# board.net
KiCad netlist of a schematic drawn in EAGLE
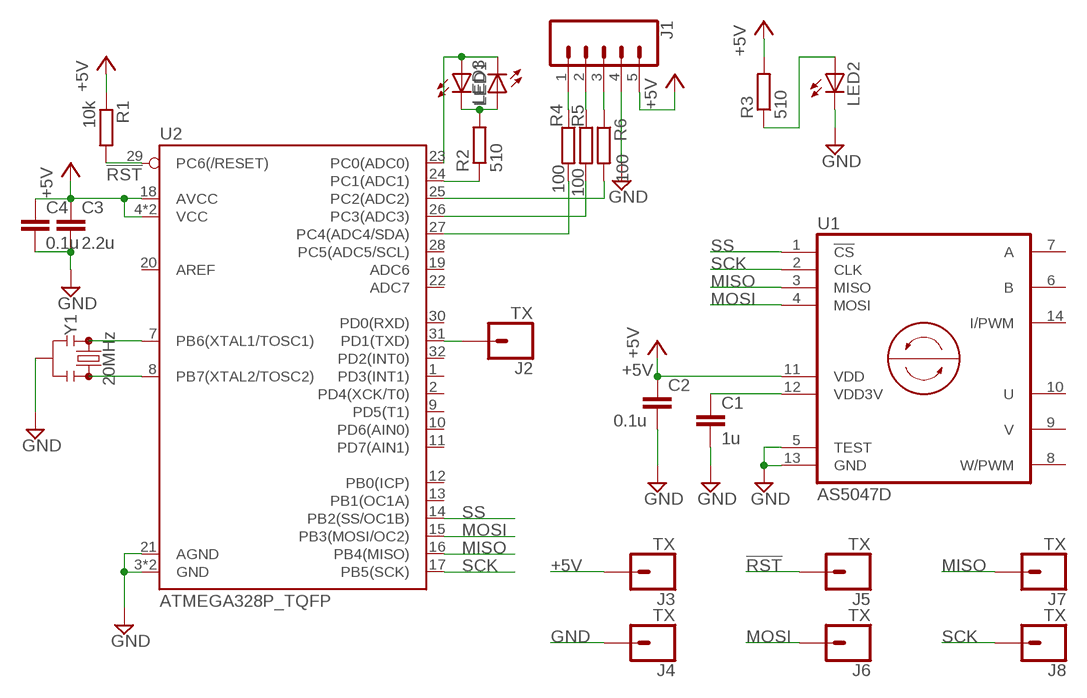
[diagram p0: schematic, sheet 1]

(export (version "E")
  (design (tool "Eeschema 10.0.6"))
  (components
    (comp (ref "C1")
      (value "1u")
      (footprint "eagle-import:C0603")
      (libsource (lib "eagle-import") (part "C-EUC0603"))
    )
    (comp (ref "C2")
      (value "0.1u")
      (footprint "eagle-import:C0603")
      (libsource (lib "eagle-import") (part "C-EUC0603"))
    )
    (comp (ref "C3")
      (value "2.2u")
      (footprint "eagle-import:C0603")
      (libsource (lib "eagle-import") (part "C-EUC0603"))
    )
    (comp (ref "C4")
      (value "0.1u")
      (footprint "eagle-import:C0603")
      (libsource (lib "eagle-import") (part "C-EUC0603"))
    )
    (comp (ref "J1")
      (value "CONN_05PTH_LONGPADS")
      (footprint "eagle-import:1X05_LONGPADS")
      (libsource (lib "eagle-import") (part "CONN_05PTH_LONGPADS"))
    )
    (comp (ref "J2")
      (value "TX")
      (footprint "eagle-import:1X01_NO_SILK")
      (libsource (lib "eagle-import") (part "CONN_01PTH_NO_SILK_YES_STOP"))
    )
    (comp (ref "J3")
      (value "TX")
      (footprint "eagle-import:1X01_NO_SILK")
      (libsource (lib "eagle-import") (part "CONN_01PTH_NO_SILK_YES_STOP"))
    )
    (comp (ref "J4")
      (value "TX")
      (footprint "eagle-import:1X01_NO_SILK")
      (libsource (lib "eagle-import") (part "CONN_01PTH_NO_SILK_YES_STOP"))
    )
    (comp (ref "J5")
      (value "TX")
      (footprint "eagle-import:1X01_NO_SILK")
      (libsource (lib "eagle-import") (part "CONN_01PTH_NO_SILK_YES_STOP"))
    )
    (comp (ref "J6")
      (value "TX")
      (footprint "eagle-import:1X01_NO_SILK")
      (libsource (lib "eagle-import") (part "CONN_01PTH_NO_SILK_YES_STOP"))
    )
    (comp (ref "J7")
      (value "TX")
      (footprint "eagle-import:1X01_NO_SILK")
      (libsource (lib "eagle-import") (part "CONN_01PTH_NO_SILK_YES_STOP"))
    )
    (comp (ref "J8")
      (value "TX")
      (footprint "eagle-import:1X01_NO_SILK")
      (libsource (lib "eagle-import") (part "CONN_01PTH_NO_SILK_YES_STOP"))
    )
    (comp (ref "LED1")
      (value "LEDSML0805")
      (footprint "eagle-import:SML0805")
      (libsource (lib "eagle-import") (part "LEDSML0805"))
    )
    (comp (ref "LED2")
      (value "LEDSML0805")
      (footprint "eagle-import:SML0805")
      (libsource (lib "eagle-import") (part "LEDSML0805"))
    )
    (comp (ref "LED3")
      (value "LEDSML0805")
      (footprint "eagle-import:SML0805")
      (libsource (lib "eagle-import") (part "LEDSML0805"))
    )
    (comp (ref "R1")
      (value "10k")
      (footprint "eagle-import:R0603")
      (libsource (lib "eagle-import") (part "R-EU_R0603"))
    )
    (comp (ref "R2")
      (value "510")
      (footprint "eagle-import:R0603")
      (libsource (lib "eagle-import") (part "R-EU_R0603"))
    )
    (comp (ref "R3")
      (value "510")
      (footprint "eagle-import:R0603")
      (libsource (lib "eagle-import") (part "R-EU_R0603"))
    )
    (comp (ref "R4")
      (value "100")
      (footprint "eagle-import:R0603")
      (libsource (lib "eagle-import") (part "R-EU_R0603"))
    )
    (comp (ref "R5")
      (value "100")
      (footprint "eagle-import:R0603")
      (libsource (lib "eagle-import") (part "R-EU_R0603"))
    )
    (comp (ref "R6")
      (value "100")
      (footprint "eagle-import:R0603")
      (libsource (lib "eagle-import") (part "R-EU_R0603"))
    )
    (comp (ref "U1")
      (value "AS5047D")
      (footprint "eagle-import:TSSOP14")
      (libsource (lib "eagle-import") (part "AS5047P"))
    )
    (comp (ref "U2")
      (value "ATMEGA328P_TQFP")
      (footprint "eagle-import:TQFP32-08")
      (libsource (lib "eagle-import") (part "ATMEGA328P_TQFP"))
    )
    (comp (ref "Y1")
      (value "20MHz")
      (footprint "eagle-import:CSTCE20M0V53-R0")
      (libsource (lib "eagle-import") (part "CSTCE20M0V53-R0SMD_3.2X1.3"))
    )
  )
  (nets
    (net (code "1") (name "+5V") (class "Default")
      (node (ref "C2") (pin "1") (pinfunction "1_1") (pintype "passive"))
      (node (ref "C3") (pin "1") (pinfunction "1_1") (pintype "passive"))
      (node (ref "C4") (pin "1") (pinfunction "1_1") (pintype "passive"))
      (node (ref "J1") (pin "5") (pinfunction "5_5") (pintype "passive"))
      (node (ref "J3") (pin "1") (pinfunction "1_1") (pintype "passive"))
      (node (ref "R1") (pin "1") (pinfunction "1_1") (pintype "passive"))
      (node (ref "R3") (pin "2") (pinfunction "2_2") (pintype "passive"))
      (node (ref "U1") (pin "11") (pinfunction "VDD_11") (pintype "power_in"))
      (node (ref "U2") (pin "18") (pinfunction "AVCC_18") (pintype "bidirectional"))
      (node (ref "U2") (pin "4") (pinfunction "VCC_4") (pintype "bidirectional"))
      (node (ref "U2") (pin "6") (pinfunction "VCC_6") (pintype "bidirectional"))
    )
    (net (code "2") (name "/MISO") (class "Default")
      (node (ref "J7") (pin "1") (pinfunction "1_1") (pintype "passive"))
      (node (ref "U1") (pin "3") (pinfunction "MISO_3") (pintype "output"))
      (node (ref "U2") (pin "16") (pinfunction "PB4(MISO)_16") (pintype "bidirectional"))
    )
    (net (code "3") (name "/MOSI") (class "Default")
      (node (ref "J6") (pin "1") (pinfunction "1_1") (pintype "passive"))
      (node (ref "U1") (pin "4") (pinfunction "MOSI_4") (pintype "input"))
      (node (ref "U2") (pin "15") (pinfunction "PB3(MOSI/OC2)_15") (pintype "bidirectional"))
    )
    (net (code "4") (name "/SCK") (class "Default")
      (node (ref "J8") (pin "1") (pinfunction "1_1") (pintype "passive"))
      (node (ref "U1") (pin "2") (pinfunction "CLK_2") (pintype "input"))
      (node (ref "U2") (pin "17") (pinfunction "PB5(SCK)_17") (pintype "bidirectional"))
    )
    (net (code "5") (name "/SS") (class "Default")
      (node (ref "U1") (pin "1") (pinfunction "~{CS}_1") (pintype "input"))
      (node (ref "U2") (pin "14") (pinfunction "PB2(SS/OC1B)_14") (pintype "bidirectional"))
    )
    (net (code "6") (name "/~{RST}") (class "Default")
      (node (ref "J5") (pin "1") (pinfunction "1_1") (pintype "passive"))
      (node (ref "R1") (pin "2") (pinfunction "2_2") (pintype "passive"))
      (node (ref "U2") (pin "29") (pinfunction "PC6(/RESET)_29") (pintype "bidirectional"))
    )
    (net (code "7") (name "GND") (class "Default")
      (node (ref "C1") (pin "2") (pinfunction "2_2") (pintype "passive"))
      (node (ref "C2") (pin "2") (pinfunction "2_2") (pintype "passive"))
      (node (ref "C3") (pin "2") (pinfunction "2_2") (pintype "passive"))
      (node (ref "C4") (pin "2") (pinfunction "2_2") (pintype "passive"))
      (node (ref "J1") (pin "4") (pinfunction "4_4") (pintype "passive"))
      (node (ref "J4") (pin "1") (pinfunction "1_1") (pintype "passive"))
      (node (ref "LED2") (pin "C") (pinfunction "C_C") (pintype "passive"))
      (node (ref "U1") (pin "13") (pinfunction "GND_13") (pintype "power_in"))
      (node (ref "U1") (pin "5") (pinfunction "TEST_5") (pintype "input"))
      (node (ref "U2") (pin "21") (pinfunction "AGND_21") (pintype "bidirectional"))
      (node (ref "U2") (pin "3") (pinfunction "GND_3") (pintype "bidirectional"))
      (node (ref "U2") (pin "5") (pinfunction "GND_5") (pintype "bidirectional"))
      (node (ref "Y1") (pin "2") (pinfunction "2_2") (pintype "passive"))
    )
    (net (code "8") (name "Net-(J1-Pad1)") (class "Default")
      (node (ref "J1") (pin "1") (pinfunction "1_1") (pintype "passive"))
      (node (ref "R4") (pin "1") (pinfunction "1_1") (pintype "passive"))
    )
    (net (code "9") (name "Net-(J1-Pad2)") (class "Default")
      (node (ref "J1") (pin "2") (pinfunction "2_2") (pintype "passive"))
      (node (ref "R5") (pin "1") (pinfunction "1_1") (pintype "passive"))
    )
    (net (code "10") (name "Net-(J1-Pad3)") (class "Default")
      (node (ref "J1") (pin "3") (pinfunction "3_3") (pintype "passive"))
      (node (ref "R6") (pin "1") (pinfunction "1_1") (pintype "passive"))
    )
    (net (code "11") (name "Net-(LED1-PadC)") (class "Default")
      (node (ref "LED1") (pin "C") (pinfunction "C_C") (pintype "passive"))
      (node (ref "LED3") (pin "A") (pinfunction "A_A") (pintype "passive"))
      (node (ref "R2") (pin "2") (pinfunction "2_2") (pintype "passive"))
    )
    (net (code "12") (name "Net-(LED2-PadA)") (class "Default")
      (node (ref "LED2") (pin "A") (pinfunction "A_A") (pintype "passive"))
      (node (ref "R3") (pin "1") (pinfunction "1_1") (pintype "passive"))
    )
    (net (code "13") (name "Net-(U1-VDD3V)") (class "Default")
      (node (ref "C1") (pin "1") (pinfunction "1_1") (pintype "passive"))
      (node (ref "U1") (pin "12") (pinfunction "VDD3V_12") (pintype "power_in"))
    )
    (net (code "14") (name "Net-(U2-PB6(XTAL1{slash}TOSC1))") (class "Default")
      (node (ref "U2") (pin "7") (pinfunction "PB6(XTAL1/TOSC1)_7") (pintype "bidirectional"))
      (node (ref "Y1") (pin "1") (pinfunction "1_1") (pintype "passive"))
    )
    (net (code "15") (name "Net-(U2-PB7(XTAL2{slash}TOSC2))") (class "Default")
      (node (ref "U2") (pin "8") (pinfunction "PB7(XTAL2/TOSC2)_8") (pintype "bidirectional"))
      (node (ref "Y1") (pin "3") (pinfunction "3_3") (pintype "passive"))
    )
    (net (code "16") (name "Net-(U2-PC0(ADC0))") (class "Default")
      (node (ref "LED1") (pin "A") (pinfunction "A_A") (pintype "passive"))
      (node (ref "LED3") (pin "C") (pinfunction "C_C") (pintype "passive"))
      (node (ref "U2") (pin "23") (pinfunction "PC0(ADC0)_23") (pintype "bidirectional"))
    )
    (net (code "17") (name "Net-(U2-PC1(ADC1))") (class "Default")
      (node (ref "R2") (pin "1") (pinfunction "1_1") (pintype "passive"))
      (node (ref "U2") (pin "24") (pinfunction "PC1(ADC1)_24") (pintype "bidirectional"))
    )
    (net (code "18") (name "Net-(U2-PC2(ADC2))") (class "Default")
      (node (ref "R6") (pin "2") (pinfunction "2_2") (pintype "passive"))
      (node (ref "U2") (pin "25") (pinfunction "PC2(ADC2)_25") (pintype "bidirectional"))
    )
    (net (code "19") (name "Net-(U2-PC3(ADC3))") (class "Default")
      (node (ref "R5") (pin "2") (pinfunction "2_2") (pintype "passive"))
      (node (ref "U2") (pin "26") (pinfunction "PC3(ADC3)_26") (pintype "bidirectional"))
    )
    (net (code "20") (name "Net-(U2-PC4(ADC4{slash}SDA))") (class "Default")
      (node (ref "R4") (pin "2") (pinfunction "2_2") (pintype "passive"))
      (node (ref "U2") (pin "27") (pinfunction "PC4(ADC4/SDA)_27") (pintype "bidirectional"))
    )
    (net (code "21") (name "Net-(U2-PD1(TXD))") (class "Default")
      (node (ref "J2") (pin "1") (pinfunction "1_1") (pintype "passive"))
      (node (ref "U2") (pin "31") (pinfunction "PD1(TXD)_31") (pintype "bidirectional"))
    )
    (net (code "22") (name "unconnected-(U1-A-Pad7)") (class "Default")
      (node (ref "U1") (pin "7") (pinfunction "A_7") (pintype "output"))
    )
    (net (code "23") (name "unconnected-(U1-B-Pad6)") (class "Default")
      (node (ref "U1") (pin "6") (pinfunction "B_6") (pintype "output"))
    )
    (net (code "24") (name "unconnected-(U1-I{slash}PWM-Pad14)") (class "Default")
      (node (ref "U1") (pin "14") (pinfunction "I/PWM_14") (pintype "output"))
    )
    (net (code "25") (name "unconnected-(U1-U-Pad10)") (class "Default")
      (node (ref "U1") (pin "10") (pinfunction "U_10") (pintype "output"))
    )
    (net (code "26") (name "unconnected-(U1-V-Pad9)") (class "Default")
      (node (ref "U1") (pin "9") (pinfunction "V_9") (pintype "output"))
    )
    (net (code "27") (name "unconnected-(U1-W{slash}PWM-Pad8)") (class "Default")
      (node (ref "U1") (pin "8") (pinfunction "W/PWM_8") (pintype "output"))
    )
    (net (code "28") (name "unconnected-(U2-ADC6-Pad19)") (class "Default")
      (node (ref "U2") (pin "19") (pinfunction "ADC6_19") (pintype "bidirectional"))
    )
    (net (code "29") (name "unconnected-(U2-ADC7-Pad22)") (class "Default")
      (node (ref "U2") (pin "22") (pinfunction "ADC7_22") (pintype "bidirectional"))
    )
    (net (code "30") (name "unconnected-(U2-AREF-Pad20)") (class "Default")
      (node (ref "U2") (pin "20") (pinfunction "AREF_20") (pintype "bidirectional"))
    )
    (net (code "31") (name "unconnected-(U2-PB0(ICP)-Pad12)") (class "Default")
      (node (ref "U2") (pin "12") (pinfunction "PB0(ICP)_12") (pintype "bidirectional"))
    )
    (net (code "32") (name "unconnected-(U2-PB1(OC1A)-Pad13)") (class "Default")
      (node (ref "U2") (pin "13") (pinfunction "PB1(OC1A)_13") (pintype "bidirectional"))
    )
    (net (code "33") (name "unconnected-(U2-PC5(ADC5{slash}SCL)-Pad28)") (class "Default")
      (node (ref "U2") (pin "28") (pinfunction "PC5(ADC5/SCL)_28") (pintype "bidirectional"))
    )
    (net (code "34") (name "unconnected-(U2-PD0(RXD)-Pad30)") (class "Default")
      (node (ref "U2") (pin "30") (pinfunction "PD0(RXD)_30") (pintype "bidirectional"))
    )
    (net (code "35") (name "unconnected-(U2-PD2(INT0)-Pad32)") (class "Default")
      (node (ref "U2") (pin "32") (pinfunction "PD2(INT0)_32") (pintype "bidirectional"))
    )
    (net (code "36") (name "unconnected-(U2-PD3(INT1)-Pad1)") (class "Default")
      (node (ref "U2") (pin "1") (pinfunction "PD3(INT1)_1") (pintype "bidirectional"))
    )
    (net (code "37") (name "unconnected-(U2-PD4(XCK{slash}T0)-Pad2)") (class "Default")
      (node (ref "U2") (pin "2") (pinfunction "PD4(XCK/T0)_2") (pintype "bidirectional"))
    )
    (net (code "38") (name "unconnected-(U2-PD5(T1)-Pad9)") (class "Default")
      (node (ref "U2") (pin "9") (pinfunction "PD5(T1)_9") (pintype "bidirectional"))
    )
    (net (code "39") (name "unconnected-(U2-PD6(AIN0)-Pad10)") (class "Default")
      (node (ref "U2") (pin "10") (pinfunction "PD6(AIN0)_10") (pintype "bidirectional"))
    )
    (net (code "40") (name "unconnected-(U2-PD7(AIN1)-Pad11)") (class "Default")
      (node (ref "U2") (pin "11") (pinfunction "PD7(AIN1)_11") (pintype "bidirectional"))
    )
  )
)
